# SMPS-Module-castellated.net
KiCad netlist of a schematic drawn in EAGLE
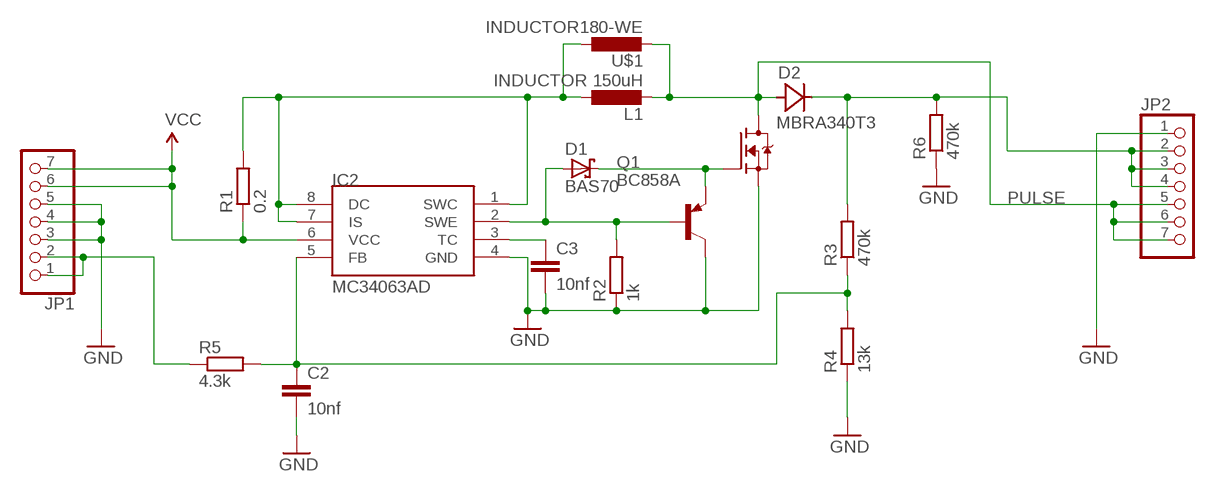
[diagram p0: schematic, sheet 1]

(export (version "E")
  (design (tool "Eeschema 10.0.6"))
  (components
    (comp (ref "C2")
      (value "10nf")
      (footprint "eagle-import:C0805")
      (libsource (lib "eagle-import") (part "C-EUC0805"))
    )
    (comp (ref "C3")
      (value "10nf")
      (footprint "eagle-import:C0805")
      (libsource (lib "eagle-import") (part "C-EUC0805"))
    )
    (comp (ref "D1")
      (value "BAS70")
      (footprint "eagle-import:SOT23")
      (libsource (lib "eagle-import") (part "BAS70"))
    )
    (comp (ref "D2")
      (value "MBRA340T3")
      (footprint "eagle-import:SMA")
      (libsource (lib "eagle-import") (part "MBRA340T3"))
    )
    (comp (ref "IC2")
      (value "MC34063AD")
      (footprint "eagle-import:SOIC8")
      (libsource (lib "eagle-import") (part "MC34063AD"))
    )
    (comp (ref "JP1")
      (value "PINHD-1X7")
      (footprint "eagle-import:1X07")
      (libsource (lib "eagle-import") (part "PINHD-1X7"))
    )
    (comp (ref "JP2")
      (value "PINHD-1X7")
      (footprint "eagle-import:1X07")
      (libsource (lib "eagle-import") (part "PINHD-1X7"))
    )
    (comp (ref "L1")
      (value "INDUCTOR 150uH")
      (footprint "eagle-import:SDR1806(BOURNS)")
      (libsource (lib "eagle-import") (part "N3D-TECH_INDUCTOR"))
    )
    (comp (ref "Q1")
      (value "BC858A")
      (footprint "eagle-import:SOT23-BEC")
      (libsource (lib "eagle-import") (part "BC858SMDA"))
    )
    (comp (ref "R1")
      (value "0.2")
      (footprint "eagle-import:R2512")
      (libsource (lib "eagle-import") (part "R-EU_R2512"))
    )
    (comp (ref "R2")
      (value "1k")
      (footprint "eagle-import:R0805")
      (libsource (lib "eagle-import") (part "R-EU_R0805"))
    )
    (comp (ref "R3")
      (value "470k")
      (footprint "eagle-import:R0805")
      (libsource (lib "eagle-import") (part "R-EU_R0805"))
    )
    (comp (ref "R4")
      (value "13k")
      (footprint "eagle-import:R0805")
      (libsource (lib "eagle-import") (part "R-EU_R0805"))
    )
    (comp (ref "R5")
      (value "4.3k")
      (footprint "eagle-import:R0805")
      (libsource (lib "eagle-import") (part "R-EU_R0805"))
    )
    (comp (ref "R6")
      (value "470k")
      (footprint "eagle-import:R0805")
      (libsource (lib "eagle-import") (part "R-EU_R0805"))
    )
    (comp (ref "U$1")
      (value "INDUCTOR180-WE")
      (footprint "eagle-import:WE180-744770218")
      (libsource (lib "eagle-import") (part "INDUCTOR180-WE"))
    )
    (comp (ref "U$2")
      (value "POWER-NFETTDSON")
      (footprint "eagle-import:PG-TDSON-8")
      (libsource (lib "eagle-import") (part "POWER-NFETTDSON"))
    )
  )
  (nets
    (net (code "1") (name "/PULSE") (class "Default")
      (node (ref "D2") (pin "A") (pinfunction "A_A") (pintype "passive"))
      (node (ref "JP2") (pin "5") (pinfunction "5_5") (pintype "passive"))
      (node (ref "JP2") (pin "6") (pinfunction "6_6") (pintype "passive"))
      (node (ref "JP2") (pin "7") (pinfunction "7_7") (pintype "passive"))
      (node (ref "L1") (pin "P$2") (pinfunction "2_P$2") (pintype "passive"))
      (node (ref "U$1") (pin "P$2") (pinfunction "2_P$2") (pintype "passive"))
      (node (ref "U$2") (pin "5") (pinfunction "D_5") (pintype "passive"))
      (node (ref "U$2") (pin "6") (pinfunction "D_6") (pintype "passive"))
      (node (ref "U$2") (pin "7") (pinfunction "D_7") (pintype "passive"))
      (node (ref "U$2") (pin "8") (pinfunction "D_8") (pintype "passive"))
      (node (ref "U$2") (pin "TH") (pinfunction "D_TH") (pintype "passive"))
    )
    (net (code "2") (name "GND") (class "Default")
      (node (ref "C2") (pin "2") (pinfunction "2_2") (pintype "passive"))
      (node (ref "C3") (pin "2") (pinfunction "2_2") (pintype "passive"))
      (node (ref "IC2") (pin "4") (pinfunction "GND_4") (pintype "passive"))
      (node (ref "JP1") (pin "3") (pinfunction "3_3") (pintype "passive"))
      (node (ref "JP1") (pin "4") (pinfunction "4_4") (pintype "passive"))
      (node (ref "JP1") (pin "5") (pinfunction "5_5") (pintype "passive"))
      (node (ref "JP2") (pin "1") (pinfunction "1_1") (pintype "passive"))
      (node (ref "Q1") (pin "C") (pinfunction "C_C") (pintype "passive"))
      (node (ref "R2") (pin "1") (pinfunction "1_1") (pintype "passive"))
      (node (ref "R4") (pin "1") (pinfunction "1_1") (pintype "passive"))
      (node (ref "R6") (pin "1") (pinfunction "1_1") (pintype "passive"))
      (node (ref "U$2") (pin "1") (pinfunction "S_1") (pintype "passive"))
      (node (ref "U$2") (pin "2") (pinfunction "S_2") (pintype "passive"))
      (node (ref "U$2") (pin "3") (pinfunction "S_3") (pintype "passive"))
    )
    (net (code "3") (name "Net-(D1-A)") (class "Default")
      (node (ref "D1") (pin "1") (pinfunction "A_1") (pintype "passive"))
      (node (ref "IC2") (pin "2") (pinfunction "SWE_2") (pintype "passive"))
      (node (ref "Q1") (pin "B") (pinfunction "B_B") (pintype "passive"))
      (node (ref "R2") (pin "2") (pinfunction "2_2") (pintype "passive"))
    )
    (net (code "4") (name "Net-(D1-C)") (class "Default")
      (node (ref "D1") (pin "3") (pinfunction "C_3") (pintype "passive"))
      (node (ref "Q1") (pin "E") (pinfunction "E_E") (pintype "passive"))
      (node (ref "U$2") (pin "4") (pinfunction "G_4") (pintype "passive"))
    )
    (net (code "5") (name "Net-(D2-PadC)") (class "Default")
      (node (ref "D2") (pin "C") (pinfunction "C_C") (pintype "passive"))
      (node (ref "JP2") (pin "2") (pinfunction "2_2") (pintype "passive"))
      (node (ref "JP2") (pin "3") (pinfunction "3_3") (pintype "passive"))
      (node (ref "JP2") (pin "4") (pinfunction "4_4") (pintype "passive"))
      (node (ref "R3") (pin "2") (pinfunction "2_2") (pintype "passive"))
      (node (ref "R6") (pin "2") (pinfunction "2_2") (pintype "passive"))
    )
    (net (code "6") (name "Net-(IC2-DC)") (class "Default")
      (node (ref "IC2") (pin "1") (pinfunction "SWC_1") (pintype "passive"))
      (node (ref "IC2") (pin "7") (pinfunction "IS_7") (pintype "passive"))
      (node (ref "IC2") (pin "8") (pinfunction "DC_8") (pintype "passive"))
      (node (ref "L1") (pin "P$1") (pinfunction "1_P$1") (pintype "passive"))
      (node (ref "R1") (pin "2") (pinfunction "2_2") (pintype "passive"))
      (node (ref "U$1") (pin "P$1") (pinfunction "1_P$1") (pintype "passive"))
    )
    (net (code "7") (name "Net-(IC2-FB)") (class "Default")
      (node (ref "C2") (pin "1") (pinfunction "1_1") (pintype "passive"))
      (node (ref "IC2") (pin "5") (pinfunction "FB_5") (pintype "passive"))
      (node (ref "R3") (pin "1") (pinfunction "1_1") (pintype "passive"))
      (node (ref "R4") (pin "2") (pinfunction "2_2") (pintype "passive"))
      (node (ref "R5") (pin "2") (pinfunction "2_2") (pintype "passive"))
    )
    (net (code "8") (name "Net-(IC2-TC)") (class "Default")
      (node (ref "C3") (pin "1") (pinfunction "1_1") (pintype "passive"))
      (node (ref "IC2") (pin "3") (pinfunction "TC_3") (pintype "passive"))
    )
    (net (code "9") (name "Net-(JP1-Pad1)") (class "Default")
      (node (ref "JP1") (pin "1") (pinfunction "1_1") (pintype "passive"))
      (node (ref "JP1") (pin "2") (pinfunction "2_2") (pintype "passive"))
      (node (ref "R5") (pin "1") (pinfunction "1_1") (pintype "passive"))
    )
    (net (code "10") (name "VCC") (class "Default")
      (node (ref "IC2") (pin "6") (pinfunction "VCC_6") (pintype "passive"))
      (node (ref "JP1") (pin "6") (pinfunction "6_6") (pintype "passive"))
      (node (ref "JP1") (pin "7") (pinfunction "7_7") (pintype "passive"))
      (node (ref "R1") (pin "1") (pinfunction "1_1") (pintype "passive"))
    )
  )
)
